# main.net
KiCad netlist of a schematic drawn in EAGLE
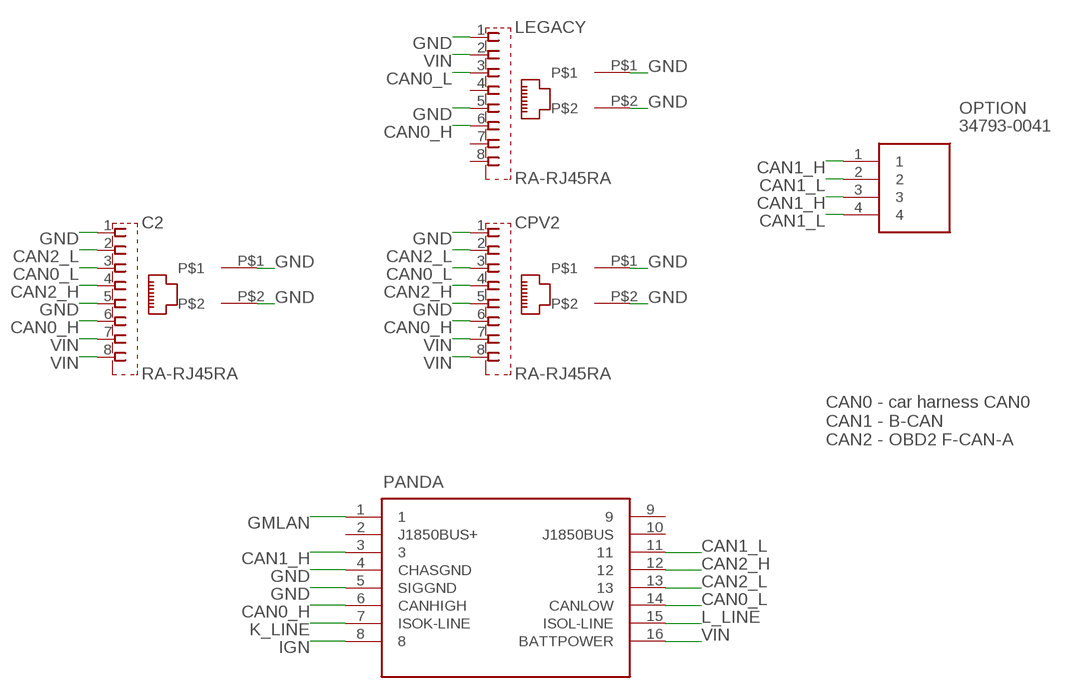
[diagram p0: schematic, sheet 1]

(export (version "E")
  (design (tool "Eeschema 10.0.6"))
  (components
    (comp (ref "C2")
      (value "RA-RJ45RA")
      (footprint "eagle-import:RA-RJ45")
      (libsource (lib "eagle-import") (part "RA-RJ45RA"))
    )
    (comp (ref "CPV2")
      (value "RA-RJ45RA")
      (footprint "eagle-import:RA-RJ45")
      (libsource (lib "eagle-import") (part "RA-RJ45RA"))
    )
    (comp (ref "LEGACY")
      (value "RA-RJ45RA")
      (footprint "eagle-import:RA-RJ45")
      (libsource (lib "eagle-import") (part "RA-RJ45RA"))
    )
    (comp (ref "OPTION")
      (value "34793-0041")
      (footprint "eagle-import:347930041")
      (fields (field (name "MOUSER_PART_NUMBER") "538-34793-0041"))
      (libsource (lib "eagle-import") (part "34793-0041"))
    )
    (comp (ref "PANDA")
      (value "OBDII-FEMALEFEMALE")
      (footprint "eagle-import:OBDII-FEMALE")
      (libsource (lib "eagle-import") (part "OBDII-FEMALEFEMALE"))
    )
  )
  (nets
    (net (code "1") (name "/CAN0_H") (class "Default")
      (node (ref "C2") (pin "6") (pinfunction "6_6") (pintype "passive"))
      (node (ref "CPV2") (pin "6") (pinfunction "6_6") (pintype "passive"))
      (node (ref "LEGACY") (pin "6") (pinfunction "6_6") (pintype "passive"))
      (node (ref "PANDA") (pin "6") (pinfunction "CANHIGH_6") (pintype "bidirectional"))
    )
    (net (code "2") (name "/CAN0_L") (class "Default")
      (node (ref "C2") (pin "3") (pinfunction "3_3") (pintype "passive"))
      (node (ref "CPV2") (pin "3") (pinfunction "3_3") (pintype "passive"))
      (node (ref "LEGACY") (pin "3") (pinfunction "3_3") (pintype "passive"))
      (node (ref "PANDA") (pin "14") (pinfunction "CANLOW_14") (pintype "bidirectional"))
    )
    (net (code "3") (name "/CAN1_H") (class "Default")
      (node (ref "OPTION") (pin "1") (pinfunction "1_1") (pintype "bidirectional"))
      (node (ref "OPTION") (pin "3") (pinfunction "3_3") (pintype "bidirectional"))
      (node (ref "PANDA") (pin "3") (pinfunction "3_3") (pintype "bidirectional"))
    )
    (net (code "4") (name "/CAN1_L") (class "Default")
      (node (ref "OPTION") (pin "2") (pinfunction "2_2") (pintype "bidirectional"))
      (node (ref "OPTION") (pin "4") (pinfunction "4_4") (pintype "bidirectional"))
      (node (ref "PANDA") (pin "11") (pinfunction "11_11") (pintype "bidirectional"))
    )
    (net (code "5") (name "/CAN2_H") (class "Default")
      (node (ref "C2") (pin "4") (pinfunction "4_4") (pintype "passive"))
      (node (ref "CPV2") (pin "4") (pinfunction "4_4") (pintype "passive"))
      (node (ref "PANDA") (pin "12") (pinfunction "12_12") (pintype "bidirectional"))
    )
    (net (code "6") (name "/CAN2_L") (class "Default")
      (node (ref "C2") (pin "2") (pinfunction "2_2") (pintype "passive"))
      (node (ref "CPV2") (pin "2") (pinfunction "2_2") (pintype "passive"))
      (node (ref "PANDA") (pin "13") (pinfunction "13_13") (pintype "bidirectional"))
    )
    (net (code "7") (name "/GMLAN") (class "Default")
      (node (ref "PANDA") (pin "1") (pinfunction "1_1") (pintype "bidirectional"))
    )
    (net (code "8") (name "/GND") (class "Default")
      (node (ref "C2") (pin "1") (pinfunction "1_1") (pintype "passive"))
      (node (ref "C2") (pin "5") (pinfunction "5_5") (pintype "passive"))
      (node (ref "C2") (pin "P$1") (pinfunction "P$1_P$1") (pintype "bidirectional"))
      (node (ref "C2") (pin "P$2") (pinfunction "P$2_P$2") (pintype "bidirectional"))
      (node (ref "CPV2") (pin "1") (pinfunction "1_1") (pintype "passive"))
      (node (ref "CPV2") (pin "5") (pinfunction "5_5") (pintype "passive"))
      (node (ref "CPV2") (pin "P$1") (pinfunction "P$1_P$1") (pintype "bidirectional"))
      (node (ref "CPV2") (pin "P$2") (pinfunction "P$2_P$2") (pintype "bidirectional"))
      (node (ref "LEGACY") (pin "1") (pinfunction "1_1") (pintype "passive"))
      (node (ref "LEGACY") (pin "5") (pinfunction "5_5") (pintype "passive"))
      (node (ref "LEGACY") (pin "P$1") (pinfunction "P$1_P$1") (pintype "bidirectional"))
      (node (ref "LEGACY") (pin "P$2") (pinfunction "P$2_P$2") (pintype "bidirectional"))
      (node (ref "PANDA") (pin "4") (pinfunction "CHASGND_4") (pintype "bidirectional"))
      (node (ref "PANDA") (pin "5") (pinfunction "SIGGND_5") (pintype "bidirectional"))
    )
    (net (code "9") (name "/IGN") (class "Default")
      (node (ref "PANDA") (pin "8") (pinfunction "8_8") (pintype "bidirectional"))
    )
    (net (code "10") (name "/K_LINE") (class "Default")
      (node (ref "PANDA") (pin "7") (pinfunction "ISOK-LINE_7") (pintype "bidirectional"))
    )
    (net (code "11") (name "/L_LINE") (class "Default")
      (node (ref "PANDA") (pin "15") (pinfunction "ISOL-LINE_15") (pintype "bidirectional"))
    )
    (net (code "12") (name "/VIN") (class "Default")
      (node (ref "C2") (pin "7") (pinfunction "7_7") (pintype "passive"))
      (node (ref "C2") (pin "8") (pinfunction "8_8") (pintype "passive"))
      (node (ref "CPV2") (pin "7") (pinfunction "7_7") (pintype "passive"))
      (node (ref "CPV2") (pin "8") (pinfunction "8_8") (pintype "passive"))
      (node (ref "LEGACY") (pin "2") (pinfunction "2_2") (pintype "passive"))
      (node (ref "PANDA") (pin "16") (pinfunction "BATTPOWER_16") (pintype "bidirectional"))
    )
    (net (code "13") (name "unconnected-(LEGACY-Pad4)") (class "Default")
      (node (ref "LEGACY") (pin "4") (pinfunction "4_4") (pintype "passive"))
    )
    (net (code "14") (name "unconnected-(LEGACY-Pad7)") (class "Default")
      (node (ref "LEGACY") (pin "7") (pinfunction "7_7") (pintype "passive"))
    )
    (net (code "15") (name "unconnected-(LEGACY-Pad8)") (class "Default")
      (node (ref "LEGACY") (pin "8") (pinfunction "8_8") (pintype "passive"))
    )
    (net (code "16") (name "unconnected-(PANDA-J1850BUS+-Pad2)") (class "Default")
      (node (ref "PANDA") (pin "2") (pinfunction "J1850BUS+_2") (pintype "bidirectional"))
    )
    (net (code "17") (name "unconnected-(PANDA-J1850BUS-Pad10)") (class "Default")
      (node (ref "PANDA") (pin "10") (pinfunction "J1850BUS_10") (pintype "bidirectional"))
    )
    (net (code "18") (name "unconnected-(PANDA-Pad9)") (class "Default")
      (node (ref "PANDA") (pin "9") (pinfunction "9_9") (pintype "bidirectional"))
    )
  )
)
